# CAN_Tranceiver.net
KiCad netlist of a schematic drawn in Altium Designer
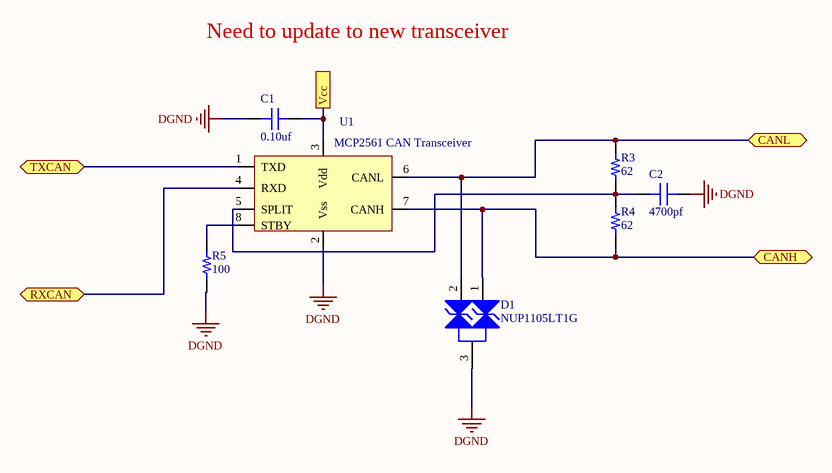
[diagram p0: CAN_Tranceiver.SchDoc]

(export (version "E")
  (design (tool "Eeschema 10.0.6"))
  (components
    (comp (ref "C1")
      (value "0.10uf")
      (footprint "CAP 0603/1608")
      (fields
        (field (name "Comment") "Capacitor MLCC 0.10uf 50V CAP 0603/1608")
        (field (name "CREATED_BY") "Nick Mah")
      )
      (libsource (lib "Altium-Lib") (part "Capacitor"))
    )
    (comp (ref "C2")
      (value "4700pf")
      (footprint "CAP 0603/1608")
      (fields
        (field (name "Comment") "Capacitor MLCC 4700pf 50V CAP 0603/1608")
        (field (name "CREATED_BY") "Nick Mah")
      )
      (libsource (lib "Altium-Lib") (part "Capacitor"))
    )
    (comp (ref "D1")
      (value "NUP1105LT1G")
      (footprint "SOT-23 (TO-236)")
      (description "ESD Protection Diode")
      (fields (field (name "POWER") "350W"))
      (libsource (lib "Altium-Lib") (part "NUP1105LT1G"))
    )
    (comp (ref "R3")
      (value "62")
      (footprint "RES 0603/1608")
      (fields
        (field (name "TOLERANCE") "5%")
        (field (name "POWER") "1/10W")
        (field (name "Comment") "Resistor 62 0603 1/10W 5%")
        (field (name "CREATED_BY") "Nick Mah")
      )
      (libsource (lib "Altium-Lib") (part "Resistor"))
    )
    (comp (ref "R4")
      (value "62")
      (footprint "RES 0603/1608")
      (fields
        (field (name "TOLERANCE") "5%")
        (field (name "POWER") "1/10W")
        (field (name "Comment") "Resistor 62 0603 1/10W 5%")
        (field (name "CREATED_BY") "Nick Mah")
      )
      (libsource (lib "Altium-Lib") (part "Resistor"))
    )
    (comp (ref "R5")
      (value "100")
      (footprint "RES 0603/1608")
      (fields
        (field (name "TOLERANCE") "10%")
        (field (name "POWER") "1/10W")
        (field (name "Comment") "Resistor 100 0603 1/10W 10%")
        (field (name "CREATED_BY") "Nick Mah")
      )
      (libsource (lib "Altium-Lib") (part "Resistor"))
    )
    (comp (ref "U1")
      (value "MCP2561 CAN Transceiver")
      (footprint "SOIC-8")
      (fields (field (name "MFRPARTNO") "MCP2561") (field (name "CREATED_BY") "Angel Delgado"))
      (libsource (lib "Altium-Lib") (part "MCP2561 CAN Transceiver"))
    )
  )
  (nets
    (net (code "1") (name "/CANH") (class "Default")
      (node (ref "D1") (pin "1") (pinfunction "K_1") (pintype "passive"))
      (node (ref "R4") (pin "2") (pinfunction "2_2") (pintype "passive"))
      (node (ref "U1") (pin "7") (pinfunction "CANH_7") (pintype "passive"))
    )
    (net (code "2") (name "/CANL") (class "Default")
      (node (ref "D1") (pin "2") (pinfunction "K_2") (pintype "passive"))
      (node (ref "R3") (pin "1") (pinfunction "1_1") (pintype "passive"))
      (node (ref "U1") (pin "6") (pinfunction "CANL_6") (pintype "passive"))
    )
    (net (code "3") (name "/RXCAN") (class "Default")
      (node (ref "U1") (pin "4") (pinfunction "RXD_4") (pintype "passive"))
    )
    (net (code "4") (name "/TXCAN") (class "Default")
      (node (ref "U1") (pin "1") (pinfunction "TXD_1") (pintype "passive"))
    )
    (net (code "5") (name "/Vcc") (class "Default")
      (node (ref "C1") (pin "2") (pinfunction "2_2") (pintype "passive"))
      (node (ref "U1") (pin "3") (pinfunction "Vdd_3") (pintype "passive"))
    )
    (net (code "6") (name "DGND") (class "Default")
      (node (ref "C1") (pin "1") (pinfunction "1_1") (pintype "passive"))
      (node (ref "C2") (pin "1") (pinfunction "1_1") (pintype "passive"))
      (node (ref "D1") (pin "3") (pinfunction "K_3") (pintype "passive"))
      (node (ref "R5") (pin "1") (pinfunction "1_1") (pintype "passive"))
      (node (ref "U1") (pin "2") (pinfunction "Vss_2") (pintype "passive"))
    )
    (net (code "7") (name "Net-(U1-SPLIT)") (class "Default")
      (node (ref "C2") (pin "2") (pinfunction "2_2") (pintype "passive"))
      (node (ref "R3") (pin "2") (pinfunction "2_2") (pintype "passive"))
      (node (ref "R4") (pin "1") (pinfunction "1_1") (pintype "passive"))
      (node (ref "U1") (pin "5") (pinfunction "SPLIT_5") (pintype "passive"))
    )
    (net (code "8") (name "Net-(U1-STBY)") (class "Default")
      (node (ref "R5") (pin "2") (pinfunction "2_2") (pintype "passive"))
      (node (ref "U1") (pin "8") (pinfunction "STBY_8") (pintype "passive"))
    )
  )
)
